# HDMI_to_RGB.net
KiCad netlist of a schematic drawn in Altium Designer
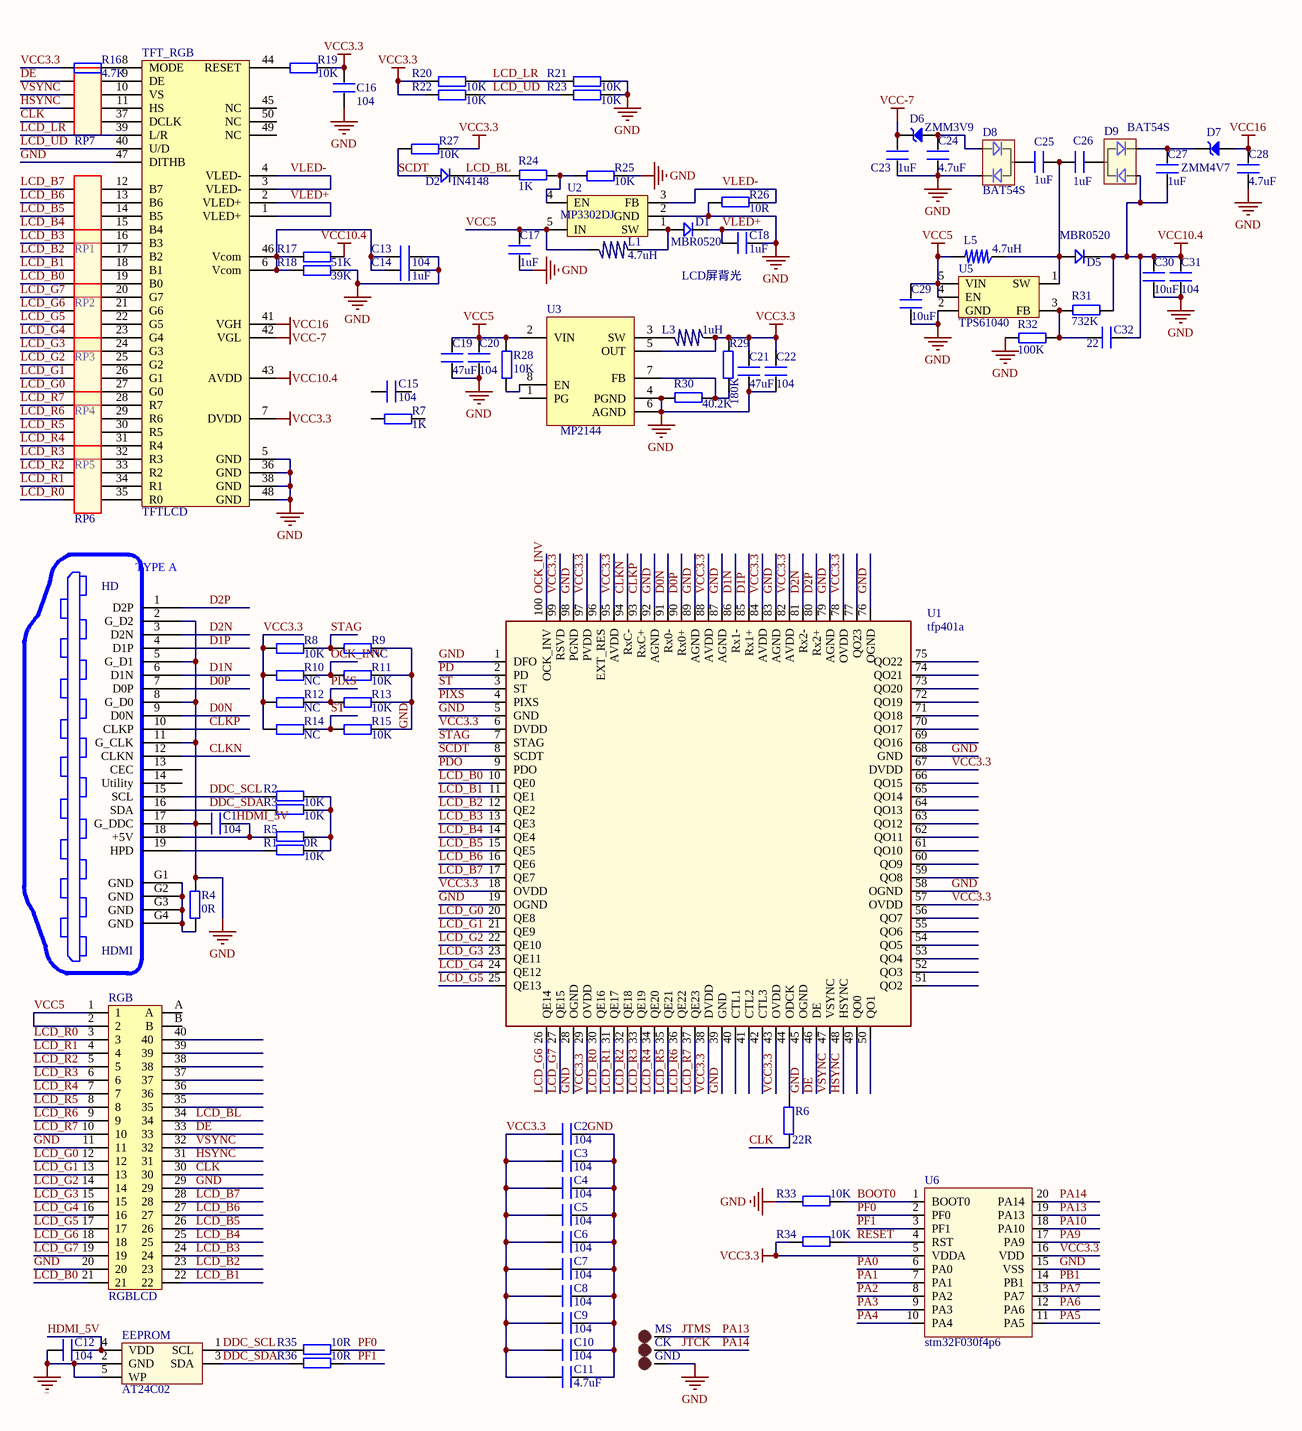
[diagram p0: HDMI_to_RGB.SchDoc]

(export (version "E")
  (design (tool "Eeschema 10.0.6"))
  (components
    (comp (ref "C1")
      (value "104")
      (footprint "C 0603_L")
      (libsource (lib "WarShip V3 STM32103封装库") (part "C"))
    )
    (comp (ref "C2")
      (value "104")
      (footprint "C 0603_L")
      (libsource (lib "WarShip V3 STM32103封装库") (part "C"))
    )
    (comp (ref "C3")
      (value "104")
      (footprint "C 0603_L")
      (libsource (lib "WarShip V3 STM32103封装库") (part "C"))
    )
    (comp (ref "C4")
      (value "104")
      (footprint "C 0603_L")
      (libsource (lib "WarShip V3 STM32103封装库") (part "C"))
    )
    (comp (ref "C5")
      (value "104")
      (footprint "C 0603_L")
      (libsource (lib "WarShip V3 STM32103封装库") (part "C"))
    )
    (comp (ref "C6")
      (value "104")
      (footprint "C 0603_L")
      (libsource (lib "WarShip V3 STM32103封装库") (part "C"))
    )
    (comp (ref "C7")
      (value "104")
      (footprint "C 0603_L")
      (libsource (lib "WarShip V3 STM32103封装库") (part "C"))
    )
    (comp (ref "C8")
      (value "104")
      (footprint "C 0603_L")
      (libsource (lib "WarShip V3 STM32103封装库") (part "C"))
    )
    (comp (ref "C9")
      (value "104")
      (footprint "C 0603_L")
      (libsource (lib "WarShip V3 STM32103封装库") (part "C"))
    )
    (comp (ref "C10")
      (value "104")
      (footprint "C 0603_L")
      (libsource (lib "WarShip V3 STM32103封装库") (part "C"))
    )
    (comp (ref "C11")
      (value "4.7uF")
      (footprint "C 0603_L")
      (libsource (lib "WarShip V3 STM32103封装库") (part "C"))
    )
    (comp (ref "C12")
      (value "104")
      (footprint "C 0603_L")
      (libsource (lib "WarShip V3 STM32103封装库") (part "C"))
    )
    (comp (ref "C13")
      (value "104")
      (footprint "C 0603_L")
      (libsource (lib "WarShip V3 STM32103封装库") (part "C"))
    )
    (comp (ref "C14")
      (value "1uF")
      (footprint "C 0603_L")
      (libsource (lib "WarShip V3 STM32103封装库") (part "C"))
    )
    (comp (ref "C15")
      (value "104")
      (footprint "C 0603_L")
      (libsource (lib "WarShip V3 STM32103封装库") (part "C"))
    )
    (comp (ref "C16")
      (value "104")
      (footprint "C 0603_L")
      (libsource (lib "WarShip V3 STM32103封装库") (part "C"))
    )
    (comp (ref "C17") (value "1uF") (footprint "C 0603_L") (libsource (lib "阿波罗STM32F4&F7底板封装库") (part "C")))
    (comp (ref "C18") (value "1uF") (footprint "C 0603_L") (libsource (lib "阿波罗STM32F4&F7底板封装库") (part "C")))
    (comp (ref "C19")
      (value "47uF")
      (footprint "C 0805_L")
      (libsource (lib "WarShip V3 STM32103封装库") (part "C"))
    )
    (comp (ref "C20")
      (value "104")
      (footprint "C 0603_L")
      (libsource (lib "WarShip V3 STM32103封装库") (part "C"))
    )
    (comp (ref "C21")
      (value "47uF")
      (footprint "C 0805_L")
      (libsource (lib "WarShip V3 STM32103封装库") (part "C"))
    )
    (comp (ref "C22")
      (value "104")
      (footprint "C 0603_L")
      (libsource (lib "WarShip V3 STM32103封装库") (part "C"))
    )
    (comp (ref "C23") (value "1uF") (footprint "C 0603_L") (libsource (lib "ALIENTEK_COMPONENT") (part "C")))
    (comp (ref "C24")
      (value "4.7uF")
      (footprint "C 0603_L")
      (libsource (lib "ALIENTEK_COMPONENT") (part "C"))
    )
    (comp (ref "C25") (value "1uF") (footprint "C 0603_L") (libsource (lib "ALIENTEK_COMPONENT") (part "C")))
    (comp (ref "C26") (value "1uF") (footprint "C 0603_L") (libsource (lib "ALIENTEK_COMPONENT") (part "C")))
    (comp (ref "C27") (value "1uF") (footprint "C 0603_L") (libsource (lib "ALIENTEK_COMPONENT") (part "C")))
    (comp (ref "C28")
      (value "4.7uF")
      (footprint "C 0603_L")
      (libsource (lib "ALIENTEK_COMPONENT") (part "C"))
    )
    (comp (ref "C29") (value "10uF") (footprint "C 0603_L") (libsource (lib "ALIENTEK_COMPONENT") (part "C")))
    (comp (ref "C30") (value "10uF") (footprint "C 0603_L") (libsource (lib "ALIENTEK_COMPONENT") (part "C")))
    (comp (ref "C31") (value "104") (footprint "C 0603_L") (libsource (lib "ALIENTEK_COMPONENT") (part "C")))
    (comp (ref "C32") (value "22") (footprint "C 0603_L") (libsource (lib "ALIENTEK_COMPONENT") (part "C")))
    (comp (ref "CK")
      (value "TEST POINT")
      (footprint "TP-1.5")
      (description "测试点")
      (libsource (lib "STM32F767核心板封装库") (part "TEST-POINT"))
    )
    (comp (ref "D1")
      (value "MBR0520")
      (footprint "二极管-整流桥:SOD-123")
      (description "1N4148")
      (libsource (lib "ATK-4.3' TFTLCD电容触摸屏模块_V1.2") (part "D"))
    )
    (comp (ref "D2")
      (value "IN4148")
      (footprint "二极管-整流桥:SOD-123")
      (description "1N4148")
      (libsource (lib "ATK-4.3' TFTLCD电容触摸屏模块_V1.2") (part "D"))
    )
    (comp (ref "D5")
      (value "MBR0520")
      (footprint "二极管-整流桥:SOD-123")
      (description "1N4148")
      (libsource (lib "ALIENTEK_COMPONENT") (part "D"))
    )
    (comp (ref "D6")
      (value "ZMM3V9")
      (footprint "DIODE_ZMMx")
      (description "ZMM3V6")
      (libsource (lib "ALIENTEK_COMPONENT") (part "ZMM3V6"))
    )
    (comp (ref "D7")
      (value "ZMM4V7")
      (footprint "DIODE_ZMMx")
      (description "ZMM3V6")
      (libsource (lib "ALIENTEK_COMPONENT") (part "ZMM3V6"))
    )
    (comp (ref "D8")
      (value "BAT54S")
      (footprint "SOT-23")
      (description "双肖特基二极管")
      (libsource (lib "") (part "BAT54S_1"))
    )
    (comp (ref "D9")
      (value "BAT54S")
      (footprint "SOT-23")
      (description "双肖特基二极管")
      (libsource (lib "ALIENTEK_COMPONENT") (part "BAT54S"))
    )
    (comp (ref "EEPROM")
      (value "AT24C02")
      (footprint "AT24C02")
      (libsource (lib "stm32f767igt6simple") (part "AT24C02"))
    )
    (comp (ref "GND")
      (value "TEST POINT")
      (footprint "TP-1.5")
      (description "测试点")
      (libsource (lib "STM32F767核心板封装库") (part "TEST-POINT"))
    )
    (comp (ref "HD")
      (value "HDMI")
      (footprint "HDMI_A")
      (libsource (lib "stm32f767igt6simple") (part "HDMI"))
    )
    (comp (ref "L1")
      (value "4.7uH")
      (footprint "NR4010")
      (libsource (lib "ATK-4.3' TFTLCD电容触摸屏模块_V1.2") (part "L"))
    )
    (comp (ref "L3") (value "1uH") (footprint "NR3015") (libsource (lib "MiniFly ") (part "L")))
    (comp (ref "L5")
      (value "4.7uH")
      (footprint "NR4010")
      (libsource (lib "ALIENTEK_COMPONENT") (part "L_SOP"))
    )
    (comp (ref "MS")
      (value "TEST POINT")
      (footprint "TP-1.5")
      (description "测试点")
      (libsource (lib "STM32F767核心板封装库") (part "TEST-POINT"))
    )
    (comp (ref "R1")
      (value "10K")
      (footprint "R 0603_L")
      (libsource (lib "WarShip V3 STM32103封装库") (part "R"))
    )
    (comp (ref "R2")
      (value "10K")
      (footprint "R 0603_L")
      (libsource (lib "WarShip V3 STM32103封装库") (part "R"))
    )
    (comp (ref "R3")
      (value "10K")
      (footprint "R 0603_L")
      (libsource (lib "WarShip V3 STM32103封装库") (part "R"))
    )
    (comp (ref "R4")
      (value "0R")
      (footprint "R 0603_L")
      (libsource (lib "WarShip V3 STM32103封装库") (part "R"))
    )
    (comp (ref "R5")
      (value "0R")
      (footprint "R 0603_L")
      (libsource (lib "WarShip V3 STM32103封装库") (part "R"))
    )
    (comp (ref "R6")
      (value "22R")
      (footprint "R 0603_L")
      (libsource (lib "WarShip V3 STM32103封装库") (part "R"))
    )
    (comp (ref "R7")
      (value "1K")
      (footprint "R 0603_L")
      (libsource (lib "WarShip V3 STM32103封装库") (part "R"))
    )
    (comp (ref "R8")
      (value "10K")
      (footprint "R 0603_L")
      (libsource (lib "WarShip V3 STM32103封装库") (part "R"))
    )
    (comp (ref "R9")
      (value "NC")
      (footprint "R 0603_L")
      (libsource (lib "WarShip V3 STM32103封装库") (part "R"))
    )
    (comp (ref "R10")
      (value "NC")
      (footprint "R 0603_L")
      (libsource (lib "WarShip V3 STM32103封装库") (part "R"))
    )
    (comp (ref "R11")
      (value "10K")
      (footprint "R 0603_L")
      (libsource (lib "WarShip V3 STM32103封装库") (part "R"))
    )
    (comp (ref "R12")
      (value "NC")
      (footprint "R 0603_L")
      (libsource (lib "WarShip V3 STM32103封装库") (part "R"))
    )
    (comp (ref "R13")
      (value "10K")
      (footprint "R 0603_L")
      (libsource (lib "WarShip V3 STM32103封装库") (part "R"))
    )
    (comp (ref "R14")
      (value "NC")
      (footprint "R 0603_L")
      (libsource (lib "WarShip V3 STM32103封装库") (part "R"))
    )
    (comp (ref "R15")
      (value "10K")
      (footprint "R 0603_L")
      (libsource (lib "WarShip V3 STM32103封装库") (part "R"))
    )
    (comp (ref "R16")
      (value "4.7K")
      (footprint "R 0603_L")
      (libsource (lib "WarShip V3 STM32103封装库") (part "R"))
    )
    (comp (ref "R17")
      (value "51K")
      (footprint "R 0603_L")
      (libsource (lib "WarShip V3 STM32103封装库") (part "R"))
    )
    (comp (ref "R18")
      (value "39K")
      (footprint "R 0603_L")
      (libsource (lib "WarShip V3 STM32103封装库") (part "R"))
    )
    (comp (ref "R19")
      (value "10K")
      (footprint "R 0603_L")
      (libsource (lib "WarShip V3 STM32103封装库") (part "R"))
    )
    (comp (ref "R20")
      (value "10K")
      (footprint "R 0603_L")
      (libsource (lib "WarShip V3 STM32103封装库") (part "R"))
    )
    (comp (ref "R21")
      (value "10K")
      (footprint "R 0603_L")
      (libsource (lib "WarShip V3 STM32103封装库") (part "R"))
    )
    (comp (ref "R22")
      (value "10K")
      (footprint "R 0603_L")
      (libsource (lib "WarShip V3 STM32103封装库") (part "R"))
    )
    (comp (ref "R23")
      (value "10K")
      (footprint "R 0603_L")
      (libsource (lib "WarShip V3 STM32103封装库") (part "R"))
    )
    (comp (ref "R24") (value "1K") (footprint "R 0603_L") (libsource (lib "阿波罗STM32F4&F7底板封装库") (part "R")))
    (comp (ref "R25") (value "10K") (footprint "R 0603_L") (libsource (lib "阿波罗STM32F4&F7底板封装库") (part "R")))
    (comp (ref "R26") (value "10R") (footprint "R 0603_L") (libsource (lib "阿波罗STM32F4&F7底板封装库") (part "R")))
    (comp (ref "R27")
      (value "10K")
      (footprint "R 0603_L")
      (libsource (lib "WarShip V3 STM32103封装库") (part "R"))
    )
    (comp (ref "R28") (value "10K") (footprint "R 0603_L") (libsource (lib "阿波罗STM32F4&F7底板封装库") (part "R")))
    (comp (ref "R29") (value "180K") (footprint "R 0603_L") (libsource (lib "电阻-电容-电感") (part "R")))
    (comp (ref "R30") (value "40.2K") (footprint "R 0603_L") (libsource (lib "电阻-电容-电感") (part "R")))
    (comp (ref "R31") (value "732K") (footprint "R 0603_L") (libsource (lib "ALIENTEK_COMPONENT") (part "R")))
    (comp (ref "R32") (value "100K") (footprint "R 0603_L") (libsource (lib "ALIENTEK_COMPONENT") (part "R")))
    (comp (ref "R33")
      (value "10K")
      (footprint "R 0603_L")
      (libsource (lib "WarShip V3 STM32103封装库") (part "R"))
    )
    (comp (ref "R34")
      (value "10K")
      (footprint "R 0603_L")
      (libsource (lib "WarShip V3 STM32103封装库") (part "R"))
    )
    (comp (ref "R35")
      (value "10R")
      (footprint "R 0603_L")
      (libsource (lib "WarShip V3 STM32103封装库") (part "R"))
    )
    (comp (ref "R36")
      (value "10R")
      (footprint "R 0603_L")
      (libsource (lib "WarShip V3 STM32103封装库") (part "R"))
    )
    (comp (ref "RGB")
      (value "RGBLCD")
      (footprint "FPC0.5 2H-WS-40P")
      (description "FPC-40P-0.5mm")
      (libsource (lib "STM32F429核心板封装库") (part "FPC-40"))
    )
    (comp (ref "RP1")
      (value "33R")
      (footprint "P_pack")
      (libsource (lib "stm32f767igt6simple") (part "R_pack"))
    )
    (comp (ref "RP2")
      (value "33R")
      (footprint "P_pack")
      (libsource (lib "stm32f767igt6simple") (part "R_pack"))
    )
    (comp (ref "RP3")
      (value "33R")
      (footprint "P_pack")
      (libsource (lib "stm32f767igt6simple") (part "R_pack"))
    )
    (comp (ref "RP4")
      (value "33R")
      (footprint "P_pack")
      (libsource (lib "stm32f767igt6simple") (part "R_pack"))
    )
    (comp (ref "RP5")
      (value "33R")
      (footprint "P_pack")
      (libsource (lib "stm32f767igt6simple") (part "R_pack"))
    )
    (comp (ref "RP6")
      (value "33R")
      (footprint "P_pack")
      (libsource (lib "stm32f767igt6simple") (part "R_pack"))
    )
    (comp (ref "RP7")
      (value "33R")
      (footprint "P_pack")
      (libsource (lib "stm32f767igt6simple") (part "R_pack"))
    )
    (comp (ref "TFT_RGB")
      (value "TFTLCD")
      (footprint "FPC-TOP50")
      (description "7' TFTLCD")
      (libsource (lib "ATK-7016&7084 7寸RGB屏模块封装库") (part "AT070TN92"))
    )
    (comp (ref "U1")
      (value "tfp401a")
      (footprint "LQFP100")
      (libsource (lib "stm32f767igt6simple") (part "tfp401a"))
    )
    (comp (ref "U2")
      (value "MP3302DJ")
      (footprint "SOT:SOT23-5L")
      (description "LCD背光IC")
      (libsource (lib "ATK-4.3' TFTLCD电容触摸屏模块_V1.2") (part "MP3302"))
    )
    (comp (ref "U3") (value "MP2144") (footprint "SOT23-8L") (libsource (lib "LDO和DCDC") (part "MP2144")))
    (comp (ref "U5")
      (value "TPS61040")
      (footprint "SOT:SOT23-5L")
      (description "DC DC Step Up IC")
      (libsource (lib "ALIENTEK_COMPONENT") (part "TPS61040"))
    )
    (comp (ref "U6")
      (value "stm32F030f4p6")
      (footprint "TSSOP20_N")
      (libsource (lib "oled_model") (part "stm32f030"))
    )
  )
  (nets
    (net (code "1") (name "/BOOT0") (class "Default")
      (node (ref "R33") (pin "1") (pintype "passive"))
      (node (ref "U6") (pin "1") (pinfunction "BOOT0_1") (pintype "passive"))
    )
    (net (code "2") (name "/CLK") (class "Default")
      (node (ref "R6") (pin "2") (pintype "passive"))
      (node (ref "RGB") (pin "30") (pinfunction "30_30") (pintype "passive"))
      (node (ref "RP7") (pin "7") (pintype "passive"))
    )
    (net (code "3") (name "/CLKN") (class "Default")
      (node (ref "HD") (pin "12") (pinfunction "CLKN_12") (pintype "passive"))
      (node (ref "U1") (pin "94") (pinfunction "RxC-_94") (pintype "passive"))
    )
    (net (code "4") (name "/CLKP") (class "Default")
      (node (ref "HD") (pin "10") (pinfunction "CLKP_10") (pintype "passive"))
      (node (ref "U1") (pin "93") (pinfunction "RxC+_93") (pintype "passive"))
    )
    (net (code "5") (name "/D0N") (class "Default")
      (node (ref "HD") (pin "9") (pinfunction "D0N_9") (pintype "passive"))
      (node (ref "U1") (pin "91") (pinfunction "Rx0-_91") (pintype "passive"))
    )
    (net (code "6") (name "/D0P") (class "Default")
      (node (ref "HD") (pin "7") (pinfunction "D0P_7") (pintype "passive"))
      (node (ref "U1") (pin "90") (pinfunction "Rx0+_90") (pintype "passive"))
    )
    (net (code "7") (name "/D1N") (class "Default")
      (node (ref "HD") (pin "6") (pinfunction "D1N_6") (pintype "passive"))
      (node (ref "U1") (pin "86") (pinfunction "Rx1-_86") (pintype "passive"))
    )
    (net (code "8") (name "/D1P") (class "Default")
      (node (ref "HD") (pin "4") (pinfunction "D1P_4") (pintype "passive"))
      (node (ref "U1") (pin "85") (pinfunction "Rx1+_85") (pintype "passive"))
    )
    (net (code "9") (name "/D2N") (class "Default")
      (node (ref "HD") (pin "3") (pinfunction "D2N_3") (pintype "passive"))
      (node (ref "U1") (pin "81") (pinfunction "Rx2-_81") (pintype "passive"))
    )
    (net (code "10") (name "/D2P") (class "Default")
      (node (ref "HD") (pin "1") (pinfunction "D2P_1") (pintype "passive"))
      (node (ref "U1") (pin "80") (pinfunction "Rx2+_80") (pintype "passive"))
    )
    (net (code "11") (name "/DDC_SCL") (class "Default")
      (node (ref "EEPROM") (pin "1") (pinfunction "SCL_1") (pintype "passive"))
      (node (ref "HD") (pin "15") (pinfunction "SCL_15") (pintype "passive"))
      (node (ref "R2") (pin "2") (pintype "passive"))
      (node (ref "R35") (pin "2") (pintype "passive"))
    )
    (net (code "12") (name "/DDC_SDA") (class "Default")
      (node (ref "EEPROM") (pin "3") (pinfunction "SDA_3") (pintype "passive"))
      (node (ref "HD") (pin "16") (pinfunction "SDA_16") (pintype "passive"))
      (node (ref "R3") (pin "2") (pintype "passive"))
      (node (ref "R36") (pin "2") (pintype "passive"))
    )
    (net (code "13") (name "/DE") (class "Default")
      (node (ref "RGB") (pin "33") (pinfunction "33_33") (pintype "passive"))
      (node (ref "RP7") (pin "1") (pinfunction "1_1") (pintype "passive"))
      (node (ref "U1") (pin "46") (pinfunction "DE_46") (pintype "passive"))
    )
    (net (code "14") (name "/HDMI_5V") (class "Default")
      (node (ref "C1") (pin "1") (pintype "passive"))
      (node (ref "C12") (pin "2") (pintype "passive"))
      (node (ref "EEPROM") (pin "4") (pinfunction "VDD_4") (pintype "passive"))
      (node (ref "HD") (pin "18") (pinfunction "+5V_18") (pintype "passive"))
      (node (ref "R5") (pin "2") (pintype "passive"))
    )
    (net (code "15") (name "/HSYNC") (class "Default")
      (node (ref "RGB") (pin "31") (pinfunction "31_31") (pintype "passive"))
      (node (ref "RP7") (pin "5") (pintype "passive"))
      (node (ref "U1") (pin "48") (pinfunction "HSYNC_48") (pintype "passive"))
    )
    (net (code "16") (name "/JTCK") (class "Default")
      (node (ref "CK") (pin "1") (pinfunction "1_1") (pintype "passive"))
      (node (ref "U6") (pin "20") (pinfunction "PA14_20") (pintype "passive"))
    )
    (net (code "17") (name "/JTMS") (class "Default")
      (node (ref "MS") (pin "1") (pinfunction "1_1") (pintype "passive"))
      (node (ref "U6") (pin "19") (pinfunction "PA13_19") (pintype "passive"))
    )
    (net (code "18") (name "/LCD_B0") (class "Default")
      (node (ref "RGB") (pin "21") (pinfunction "21_21") (pintype "passive"))
      (node (ref "RP2") (pin "7") (pintype "passive"))
      (node (ref "U1") (pin "10") (pinfunction "QE0_10") (pintype "passive"))
    )
    (net (code "19") (name "/LCD_B1") (class "Default")
      (node (ref "RGB") (pin "22") (pinfunction "22_22") (pintype "passive"))
      (node (ref "RP2") (pin "5") (pintype "passive"))
      (node (ref "U1") (pin "11") (pinfunction "QE1_11") (pintype "passive"))
    )
    (net (code "20") (name "/LCD_B2") (class "Default")
      (node (ref "RGB") (pin "23") (pinfunction "23_23") (pintype "passive"))
      (node (ref "RP2") (pin "3") (pintype "passive"))
      (node (ref "U1") (pin "12") (pinfunction "QE2_12") (pintype "passive"))
    )
    (net (code "21") (name "/LCD_B3") (class "Default")
      (node (ref "RGB") (pin "24") (pinfunction "24_24") (pintype "passive"))
      (node (ref "RP2") (pin "1") (pinfunction "1_1") (pintype "passive"))
      (node (ref "U1") (pin "13") (pinfunction "QE3_13") (pintype "passive"))
    )
    (net (code "22") (name "/LCD_B4") (class "Default")
      (node (ref "RGB") (pin "25") (pinfunction "25_25") (pintype "passive"))
      (node (ref "RP1") (pin "7") (pintype "passive"))
      (node (ref "U1") (pin "14") (pinfunction "QE4_14") (pintype "passive"))
    )
    (net (code "23") (name "/LCD_B5") (class "Default")
      (node (ref "RGB") (pin "26") (pinfunction "26_26") (pintype "passive"))
      (node (ref "RP1") (pin "5") (pintype "passive"))
      (node (ref "U1") (pin "15") (pinfunction "QE5_15") (pintype "passive"))
    )
    (net (code "24") (name "/LCD_B6") (class "Default")
      (node (ref "RGB") (pin "27") (pinfunction "27_27") (pintype "passive"))
      (node (ref "RP1") (pin "3") (pintype "passive"))
      (node (ref "U1") (pin "16") (pinfunction "QE6_16") (pintype "passive"))
    )
    (net (code "25") (name "/LCD_B7") (class "Default")
      (node (ref "RGB") (pin "28") (pinfunction "28_28") (pintype "passive"))
      (node (ref "RP1") (pin "1") (pinfunction "1_1") (pintype "passive"))
      (node (ref "U1") (pin "17") (pinfunction "QE7_17") (pintype "passive"))
    )
    (net (code "26") (name "/LCD_BL") (class "Default")
      (node (ref "D2") (pin "2") (pintype "passive"))
      (node (ref "R24") (pin "2") (pintype "passive"))
      (node (ref "RGB") (pin "34") (pinfunction "34_34") (pintype "passive"))
    )
    (net (code "27") (name "/LCD_G0") (class "Default")
      (node (ref "RGB") (pin "12") (pinfunction "12_12") (pintype "passive"))
      (node (ref "RP4") (pin "7") (pintype "passive"))
      (node (ref "U1") (pin "20") (pinfunction "QE8_20") (pintype "passive"))
    )
    (net (code "28") (name "/LCD_G1") (class "Default")
      (node (ref "RGB") (pin "13") (pinfunction "13_13") (pintype "passive"))
      (node (ref "RP4") (pin "5") (pintype "passive"))
      (node (ref "U1") (pin "21") (pinfunction "QE9_21") (pintype "passive"))
    )
    (net (code "29") (name "/LCD_G2") (class "Default")
      (node (ref "RGB") (pin "14") (pinfunction "14_14") (pintype "passive"))
      (node (ref "RP4") (pin "3") (pintype "passive"))
      (node (ref "U1") (pin "22") (pinfunction "QE10_22") (pintype "passive"))
    )
    (net (code "30") (name "/LCD_G3") (class "Default")
      (node (ref "RGB") (pin "15") (pinfunction "15_15") (pintype "passive"))
      (node (ref "RP4") (pin "1") (pinfunction "1_1") (pintype "passive"))
      (node (ref "U1") (pin "23") (pinfunction "QE11_23") (pintype "passive"))
    )
    (net (code "31") (name "/LCD_G4") (class "Default")
      (node (ref "RGB") (pin "16") (pinfunction "16_16") (pintype "passive"))
      (node (ref "RP3") (pin "7") (pintype "passive"))
      (node (ref "U1") (pin "24") (pinfunction "QE12_24") (pintype "passive"))
    )
    (net (code "32") (name "/LCD_G5") (class "Default")
      (node (ref "RGB") (pin "17") (pinfunction "17_17") (pintype "passive"))
      (node (ref "RP3") (pin "5") (pintype "passive"))
      (node (ref "U1") (pin "25") (pinfunction "QE13_25") (pintype "passive"))
    )
    (net (code "33") (name "/LCD_G6") (class "Default")
      (node (ref "RGB") (pin "18") (pinfunction "18_18") (pintype "passive"))
      (node (ref "RP3") (pin "3") (pintype "passive"))
      (node (ref "U1") (pin "26") (pinfunction "QE14_26") (pintype "passive"))
    )
    (net (code "34") (name "/LCD_G7") (class "Default")
      (node (ref "RGB") (pin "19") (pinfunction "19_19") (pintype "passive"))
      (node (ref "RP3") (pin "1") (pinfunction "1_1") (pintype "passive"))
      (node (ref "U1") (pin "27") (pinfunction "QE15_27") (pintype "passive"))
    )
    (net (code "35") (name "/LCD_LR") (class "Default")
      (node (ref "R20") (pin "2") (pintype "passive"))
      (node (ref "R21") (pin "1") (pintype "passive"))
      (node (ref "TFT_RGB") (pin "39") (pinfunction "L/R_39") (pintype "passive"))
    )
    (net (code "36") (name "/LCD_R0") (class "Default")
      (node (ref "RGB") (pin "3") (pinfunction "3_3") (pintype "passive"))
      (node (ref "RP6") (pin "7") (pintype "passive"))
      (node (ref "U1") (pin "30") (pinfunction "QE16_30") (pintype "passive"))
    )
    (net (code "37") (name "/LCD_R1") (class "Default")
      (node (ref "RGB") (pin "4") (pinfunction "4_4") (pintype "passive"))
      (node (ref "RP6") (pin "5") (pintype "passive"))
      (node (ref "U1") (pin "31") (pinfunction "QE17_31") (pintype "passive"))
    )
    (net (code "38") (name "/LCD_R2") (class "Default")
      (node (ref "RGB") (pin "5") (pinfunction "5_5") (pintype "passive"))
      (node (ref "RP6") (pin "3") (pintype "passive"))
      (node (ref "U1") (pin "32") (pinfunction "QE18_32") (pintype "passive"))
    )
    (net (code "39") (name "/LCD_R3") (class "Default")
      (node (ref "RGB") (pin "6") (pinfunction "6_6") (pintype "passive"))
      (node (ref "RP6") (pin "1") (pinfunction "1_1") (pintype "passive"))
      (node (ref "U1") (pin "33") (pinfunction "QE19_33") (pintype "passive"))
    )
    (net (code "40") (name "/LCD_R4") (class "Default")
      (node (ref "RGB") (pin "7") (pinfunction "7_7") (pintype "passive"))
      (node (ref "RP5") (pin "7") (pintype "passive"))
      (node (ref "U1") (pin "34") (pinfunction "QE20_34") (pintype "passive"))
    )
    (net (code "41") (name "/LCD_R5") (class "Default")
      (node (ref "RGB") (pin "8") (pinfunction "8_8") (pintype "passive"))
      (node (ref "RP5") (pin "5") (pintype "passive"))
      (node (ref "U1") (pin "35") (pinfunction "QE21_35") (pintype "passive"))
    )
    (net (code "42") (name "/LCD_R6") (class "Default")
      (node (ref "RGB") (pin "9") (pinfunction "9_9") (pintype "passive"))
      (node (ref "RP5") (pin "3") (pintype "passive"))
      (node (ref "U1") (pin "36") (pinfunction "QE22_36") (pintype "passive"))
    )
    (net (code "43") (name "/LCD_R7") (class "Default")
      (node (ref "RGB") (pin "10") (pinfunction "10_10") (pintype "passive"))
      (node (ref "RP5") (pin "1") (pinfunction "1_1") (pintype "passive"))
      (node (ref "U1") (pin "37") (pinfunction "QE23_37") (pintype "passive"))
    )
    (net (code "44") (name "/LCD_UD") (class "Default")
      (node (ref "R22") (pin "2") (pintype "passive"))
      (node (ref "R23") (pin "1") (pintype "passive"))
      (node (ref "TFT_RGB") (pin "40") (pinfunction "U/D_40") (pintype "passive"))
    )
    (net (code "45") (name "/OCK_INV") (class "Default")
      (node (ref "R10") (pin "2") (pintype "passive"))
      (node (ref "R11") (pin "1") (pintype "passive"))
      (node (ref "U1") (pin "100") (pinfunction "OCK_INV_100") (pintype "passive"))
    )
    (net (code "46") (name "/PA0") (class "Default")
      (node (ref "U6") (pin "6") (pinfunction "PA0_6") (pintype "passive"))
    )
    (net (code "47") (name "/PA1") (class "Default")
      (node (ref "U6") (pin "7") (pinfunction "PA1_7") (pintype "passive"))
    )
    (net (code "48") (name "/PA2") (class "Default")
      (node (ref "U6") (pin "8") (pinfunction "PA2_8") (pintype "passive"))
    )
    (net (code "49") (name "/PA3") (class "Default")
      (node (ref "U6") (pin "9") (pinfunction "PA3_9") (pintype "passive"))
    )
    (net (code "50") (name "/PA4") (class "Default")
      (node (ref "U6") (pin "10") (pinfunction "PA4_10") (pintype "passive"))
    )
    (net (code "51") (name "/PA5") (class "Default")
      (node (ref "U6") (pin "11") (pinfunction "PA5_11") (pintype "passive"))
    )
    (net (code "52") (name "/PA6") (class "Default")
      (node (ref "U6") (pin "12") (pinfunction "PA6_12") (pintype "passive"))
    )
    (net (code "53") (name "/PA7") (class "Default")
      (node (ref "U6") (pin "13") (pinfunction "PA7_13") (pintype "passive"))
    )
    (net (code "54") (name "/PA9") (class "Default")
      (node (ref "U6") (pin "17") (pinfunction "PA9_17") (pintype "passive"))
    )
    (net (code "55") (name "/PA10") (class "Default")
      (node (ref "U6") (pin "18") (pinfunction "PA10_18") (pintype "passive"))
    )
    (net (code "56") (name "/PB1") (class "Default")
      (node (ref "U6") (pin "14") (pinfunction "PB1_14") (pintype "passive"))
    )
    (net (code "57") (name "/PD") (class "Default")
      (node (ref "U1") (pin "2") (pinfunction "PD_2") (pintype "passive"))
    )
    (net (code "58") (name "/PDO") (class "Default")
      (node (ref "U1") (pin "9") (pinfunction "PDO_9") (pintype "passive"))
    )
    (net (code "59") (name "/PF0") (class "Default")
      (node (ref "R35") (pin "1") (pintype "passive"))
      (node (ref "U6") (pin "2") (pinfunction "PF0_2") (pintype "passive"))
    )
    (net (code "60") (name "/PF1") (class "Default")
      (node (ref "R36") (pin "1") (pintype "passive"))
      (node (ref "U6") (pin "3") (pinfunction "PF1_3") (pintype "passive"))
    )
    (net (code "61") (name "/PIXS") (class "Default")
      (node (ref "R12") (pin "2") (pintype "passive"))
      (node (ref "R13") (pin "1") (pintype "passive"))
      (node (ref "U1") (pin "4") (pinfunction "PIXS_4") (pintype "passive"))
    )
    (net (code "62") (name "/RESET") (class "Default")
      (node (ref "R34") (pin "1") (pintype "passive"))
      (node (ref "U6") (pin "4") (pinfunction "RST_4") (pintype "passive"))
    )
    (net (code "63") (name "/SCDT") (class "Default")
      (node (ref "D2") (pin "1") (pintype "passive"))
      (node (ref "R27") (pin "1") (pintype "passive"))
      (node (ref "U1") (pin "8") (pinfunction "SCDT_8") (pintype "passive"))
    )
    (net (code "64") (name "/ST") (class "Default")
      (node (ref "R14") (pin "2") (pintype "passive"))
      (node (ref "R15") (pin "1") (pintype "passive"))
      (node (ref "U1") (pin "3") (pinfunction "ST_3") (pintype "passive"))
    )
    (net (code "65") (name "/STAG") (class "Default")
      (node (ref "R8") (pin "2") (pintype "passive"))
      (node (ref "R9") (pin "1") (pintype "passive"))
      (node (ref "U1") (pin "7") (pinfunction "STAG_7") (pintype "passive"))
    )
    (net (code "66") (name "/VLED+") (class "Default")
      (node (ref "C18") (pin "2") (pintype "passive"))
      (node (ref "D1") (pin "2") (pintype "passive"))
      (node (ref "TFT_RGB") (pin "1") (pinfunction "VLED+_1") (pintype "passive"))
      (node (ref "TFT_RGB") (pin "2") (pinfunction "VLED+_2") (pintype "passive"))
    )
    (net (code "67") (name "/VLED-") (class "Default")
      (node (ref "R26") (pin "1") (pintype "passive"))
      (node (ref "TFT_RGB") (pin "3") (pinfunction "VLED-_3") (pintype "passive"))
      (node (ref "TFT_RGB") (pin "4") (pinfunction "VLED-_4") (pintype "passive"))
      (node (ref "U2") (pin "3") (pinfunction "FB_3") (pintype "passive"))
    )
    (net (code "68") (name "/VSYNC") (class "Default")
      (node (ref "RGB") (pin "32") (pinfunction "32_32") (pintype "passive"))
      (node (ref "RP7") (pin "3") (pintype "passive"))
      (node (ref "U1") (pin "47") (pinfunction "VSYNC_47") (pintype "passive"))
    )
    (net (code "69") (name "GND") (class "Default")
      (node (ref "C1") (pin "2") (pintype "passive"))
      (node (ref "C10") (pin "1") (pintype "passive"))
      (node (ref "C11") (pin "1") (pintype "passive"))
      (node (ref "C12") (pin "1") (pintype "passive"))
      (node (ref "C13") (pin "2") (pintype "passive"))
      (node (ref "C14") (pin "2") (pintype "passive"))
      (node (ref "C16") (pin "1") (pintype "passive"))
      (node (ref "C17") (pin "1") (pintype "passive"))
      (node (ref "C18") (pin "1") (pintype "passive"))
      (node (ref "C19") (pin "1") (pintype "passive"))
      (node (ref "C2") (pin "1") (pintype "passive"))
      (node (ref "C20") (pin "1") (pintype "passive"))
      (node (ref "C21") (pin "1") (pintype "passive"))
      (node (ref "C22") (pin "1") (pintype "passive"))
      (node (ref "C23") (pin "2") (pintype "passive"))
      (node (ref "C24") (pin "2") (pintype "passive"))
      (node (ref "C28") (pin "1") (pintype "passive"))
      (node (ref "C29") (pin "1") (pintype "passive"))
      (node (ref "C3") (pin "1") (pintype "passive"))
      (node (ref "C30") (pin "1") (pintype "passive"))
      (node (ref "C31") (pin "2") (pintype "passive"))
      (node (ref "C4") (pin "1") (pintype "passive"))
      (node (ref "C5") (pin "1") (pintype "passive"))
      (node (ref "C6") (pin "1") (pintype "passive"))
      (node (ref "C7") (pin "1") (pintype "passive"))
      (node (ref "C8") (pin "1") (pintype "passive"))
      (node (ref "C9") (pin "1") (pintype "passive"))
      (node (ref "D8") (pin "2") (pintype "passive"))
      (node (ref "EEPROM") (pin "2") (pinfunction "GND_2") (pintype "passive"))
      (node (ref "EEPROM") (pin "5") (pinfunction "WP_5") (pintype "passive"))
      (node (ref "GND") (pin "1") (pinfunction "1_1") (pintype "passive"))
      (node (ref "HD") (pin "11") (pinfunction "G_CLK_11") (pintype "passive"))
      (node (ref "HD") (pin "17") (pinfunction "G_DDC_17") (pintype "passive"))
      (node (ref "HD") (pin "2") (pinfunction "G_D2_2") (pintype "passive"))
      (node (ref "HD") (pin "5") (pinfunction "G_D1_5") (pintype "passive"))
      (node (ref "HD") (pin "8") (pinfunction "G_D0_8") (pintype "passive"))
      (node (ref "R11") (pin "2") (pintype "passive"))
      (node (ref "R13") (pin "2") (pintype "passive"))
      (node (ref "R15") (pin "2") (pintype "passive"))
      (node (ref "R18") (pin "2") (pintype "passive"))
      (node (ref "R21") (pin "2") (pintype "passive"))
      (node (ref "R23") (pin "2") (pintype "passive"))
      (node (ref "R25") (pin "2") (pintype "passive"))
      (node (ref "R26") (pin "2") (pintype "passive"))
      (node (ref "R30") (pin "2") (pintype "passive"))
      (node (ref "R32") (pin "1") (pintype "passive"))
      (node (ref "R33") (pin "2") (pintype "passive"))
      (node (ref "R4") (pin "1") (pintype "passive"))
      (node (ref "R9") (pin "2") (pintype "passive"))
      (node (ref "RGB") (pin "11") (pinfunction "11_11") (pintype "passive"))
      (node (ref "RGB") (pin "20") (pinfunction "20_20") (pintype "passive"))
      (node (ref "RGB") (pin "29") (pinfunction "29_29") (pintype "passive"))
      (node (ref "TFT_RGB") (pin "36") (pinfunction "GND_36") (pintype "passive"))
      (node (ref "TFT_RGB") (pin "38") (pinfunction "GND_38") (pintype "passive"))
      (node (ref "TFT_RGB") (pin "47") (pinfunction "DITHB_47") (pintype "passive"))
      (node (ref "TFT_RGB") (pin "48") (pinfunction "GND_48") (pintype "passive"))
      (node (ref "TFT_RGB") (pin "5") (pinfunction "GND_5") (pintype "passive"))
      (node (ref "U1") (pin "1") (pinfunction "DFO_1") (pintype "passive"))
      (node (ref "U1") (pin "19") (pinfunction "OGND_19") (pintype "passive"))
      (node (ref "U1") (pin "28") (pinfunction "OGND_28") (pintype "passive"))
      (node (ref "U1") (pin "39") (pinfunction "GND_39") (pintype "passive"))
      (node (ref "U1") (pin "45") (pinfunction "OGND_45") (pintype "passive"))
      (node (ref "U1") (pin "5") (pinfunction "GND_5") (pintype "passive"))
      (node (ref "U1") (pin "58") (pinfunction "OGND_58") (pintype "passive"))
      (node (ref "U1") (pin "68") (pinfunction "GND_68") (pintype "passive"))
      (node (ref "U1") (pin "76") (pinfunction "OGND_76") (pintype "passive"))
      (node (ref "U1") (pin "79") (pinfunction "AGND_79") (pintype "passive"))
      (node (ref "U1") (pin "83") (pinfunction "AGND_83") (pintype "passive"))
      (node (ref "U1") (pin "87") (pinfunction "AGND_87") (pintype "passive"))
      (node (ref "U1") (pin "89") (pinfunction "AGND_89") (pintype "passive"))
      (node (ref "U1") (pin "92") (pinfunction "AGND_92") (pintype "passive"))
      (node (ref "U1") (pin "98") (pinfunction "PGND_98") (pintype "passive"))
      (node (ref "U2") (pin "2") (pinfunction "GND_2") (pintype "passive"))
      (node (ref "U3") (pin "4") (pinfunction "PGND_4") (pintype "passive"))
      (node (ref "U3") (pin "6") (pinfunction "AGND_6") (pintype "passive"))
      (node (ref "U5") (pin "2") (pinfunction "GND_2") (pintype "passive"))
      (node (ref "U6") (pin "15") (pinfunction "VSS_15") (pintype "passive"))
    )
    (net (code "70") (name "Net-(C13-Pad1)") (class "Default")
      (node (ref "C13") (pin "1") (pintype "passive"))
      (node (ref "C14") (pin "1") (pintype "passive"))
      (node (ref "R17") (pin "1") (pintype "passive"))
      (node (ref "R18") (pin "1") (pintype "passive"))
      (node (ref "TFT_RGB") (pin "46") (pinfunction "Vcom_46") (pintype "passive"))
      (node (ref "TFT_RGB") (pin "6") (pinfunction "Vcom_6") (pintype "passive"))
    )
    (net (code "71") (name "Net-(C24-Pad1)") (class "Default")
      (node (ref "C24") (pin "1") (pintype "passive"))
      (node (ref "D6") (pin "1") (pintype "passive"))
      (node (ref "D8") (pin "1") (pintype "passive"))
    )
    (net (code "72") (name "Net-(C25-Pad1)") (class "Default")
      (node (ref "C25") (pin "1") (pintype "passive"))
      (node (ref "D8") (pin "3") (pintype "passive"))
    )
    (net (code "73") (name "Net-(C26-Pad2)") (class "Default")
      (node (ref "C26") (pin "2") (pintype "passive"))
      (node (ref "D9") (pin "3") (pintype "passive"))
    )
    (net (code "74") (name "Net-(C27-Pad2)") (class "Default")
      (node (ref "C27") (pin "2") (pintype "passive"))
      (node (ref "D7") (pin "2") (pintype "passive"))
      (node (ref "D9") (pin "2") (pintype "passive"))
    )
    (net (code "75") (name "Net-(HD-GND-PadG1)") (class "Default")
      (node (ref "HD") (pin "G1") (pinfunction "GND_G1") (pintype "passive"))
      (node (ref "HD") (pin "G2") (pinfunction "GND_G2") (pintype "passive"))
      (node (ref "HD") (pin "G3") (pinfunction "GND_G3") (pintype "passive"))
      (node (ref "HD") (pin "G4") (pinfunction "GND_G4") (pintype "passive"))
      (node (ref "R4") (pin "2") (pintype "passive"))
    )
    (net (code "76") (name "Net-(HD-HPD)") (class "Default")
      (node (ref "HD") (pin "19") (pinfunction "HPD_19") (pintype "passive"))
      (node (ref "R1") (pin "2") (pintype "passive"))
    )
    (net (code "77") (name "Net-(R1-Pad1)") (class "Default")
      (node (ref "R1") (pin "1") (pintype "passive"))
      (node (ref "R2") (pin "1") (pintype "passive"))
      (node (ref "R3") (pin "1") (pintype "passive"))
      (node (ref "R5") (pin "1") (pintype "passive"))
    )
    (net (code "78") (name "Net-(TFT_RGB-B0)") (class "Default")
      (node (ref "RP2") (pin "8") (pintype "passive"))
      (node (ref "TFT_RGB") (pin "19") (pinfunction "B0_19") (pintype "passive"))
    )
    (net (code "79") (name "Net-(TFT_RGB-B1)") (class "Default")
      (node (ref "RP2") (pin "6") (pintype "passive"))
      (node (ref "TFT_RGB") (pin "18") (pinfunction "B1_18") (pintype "passive"))
    )
    (net (code "80") (name "Net-(TFT_RGB-B2)") (class "Default")
      (node (ref "RP2") (pin "4") (pintype "passive"))
      (node (ref "TFT_RGB") (pin "17") (pinfunction "B2_17") (pintype "passive"))
    )
    (net (code "81") (name "Net-(TFT_RGB-B3)") (class "Default")
      (node (ref "RP2") (pin "2") (pintype "passive"))
      (node (ref "TFT_RGB") (pin "16") (pinfunction "B3_16") (pintype "passive"))
    )
    (net (code "82") (name "Net-(TFT_RGB-B4)") (class "Default")
      (node (ref "RP1") (pin "8") (pintype "passive"))
      (node (ref "TFT_RGB") (pin "15") (pinfunction "B4_15") (pintype "passive"))
    )
    (net (code "83") (name "Net-(TFT_RGB-B5)") (class "Default")
      (node (ref "RP1") (pin "6") (pintype "passive"))
      (node (ref "TFT_RGB") (pin "14") (pinfunction "B5_14") (pintype "passive"))
    )
    (net (code "84") (name "Net-(TFT_RGB-B6)") (class "Default")
      (node (ref "RP1") (pin "4") (pintype "passive"))
      (node (ref "TFT_RGB") (pin "13") (pinfunction "B6_13") (pintype "passive"))
    )
    (net (code "85") (name "Net-(TFT_RGB-B7)") (class "Default")
      (node (ref "RP1") (pin "2") (pintype "passive"))
      (node (ref "TFT_RGB") (pin "12") (pinfunction "B7_12") (pintype "passive"))
    )
    (net (code "86") (name "Net-(TFT_RGB-DCLK)") (class "Default")
      (node (ref "RP7") (pin "8") (pintype "passive"))
      (node (ref "TFT_RGB") (pin "37") (pinfunction "DCLK_37") (pintype "passive"))
    )
    (net (code "87") (name "Net-(TFT_RGB-DE)") (class "Default")
      (node (ref "RP7") (pin "2") (pintype "passive"))
      (node (ref "TFT_RGB") (pin "9") (pinfunction "DE_9") (pintype "passive"))
    )
    (net (code "88") (name "Net-(TFT_RGB-G0)") (class "Default")
      (node (ref "RP4") (pin "8") (pintype "passive"))
      (node (ref "TFT_RGB") (pin "27") (pinfunction "G0_27") (pintype "passive"))
    )
    (net (code "89") (name "Net-(TFT_RGB-G1)") (class "Default")
      (node (ref "RP4") (pin "6") (pintype "passive"))
      (node (ref "TFT_RGB") (pin "26") (pinfunction "G1_26") (pintype "passive"))
    )
    (net (code "90") (name "Net-(TFT_RGB-G2)") (class "Default")
      (node (ref "RP4") (pin "4") (pintype "passive"))
      (node (ref "TFT_RGB") (pin "25") (pinfunction "G2_25") (pintype "passive"))
    )
    (net (code "91") (name "Net-(TFT_RGB-G3)") (class "Default")
      (node (ref "RP4") (pin "2") (pintype "passive"))
      (node (ref "TFT_RGB") (pin "24") (pinfunction "G3_24") (pintype "passive"))
    )
    (net (code "92") (name "Net-(TFT_RGB-G4)") (class "Default")
      (node (ref "RP3") (pin "8") (pintype "passive"))
      (node (ref "TFT_RGB") (pin "23") (pinfunction "G4_23") (pintype "passive"))
    )
    (net (code "93") (name "Net-(TFT_RGB-G5)") (class "Default")
      (node (ref "RP3") (pin "6") (pintype "passive"))
      (node (ref "TFT_RGB") (pin "22") (pinfunction "G5_22") (pintype "passive"))
    )
    (net (code "94") (name "Net-(TFT_RGB-G6)") (class "Default")
      (node (ref "RP3") (pin "4") (pintype "passive"))
      (node (ref "TFT_RGB") (pin "21") (pinfunction "G6_21") (pintype "passive"))
    )
    (net (code "95") (name "Net-(TFT_RGB-G7)") (class "Default")
      (node (ref "RP3") (pin "2") (pintype "passive"))
      (node (ref "TFT_RGB") (pin "20") (pinfunction "G7_20") (pintype "passive"))
    )
    (net (code "96") (name "Net-(TFT_RGB-HS)") (class "Default")
      (node (ref "RP7") (pin "6") (pintype "passive"))
      (node (ref "TFT_RGB") (pin "11") (pinfunction "HS_11") (pintype "passive"))
    )
    (net (code "97") (name "Net-(TFT_RGB-MODE)") (class "Default")
      (node (ref "R16") (pin "2") (pintype "passive"))
      (node (ref "TFT_RGB") (pin "8") (pinfunction "MODE_8") (pintype "passive"))
    )
    (net (code "98") (name "Net-(TFT_RGB-R0)") (class "Default")
      (node (ref "RP6") (pin "8") (pintype "passive"))
      (node (ref "TFT_RGB") (pin "35") (pinfunction "R0_35") (pintype "passive"))
    )
    (net (code "99") (name "Net-(TFT_RGB-R1)") (class "Default")
      (node (ref "RP6") (pin "6") (pintype "passive"))
      (node (ref "TFT_RGB") (pin "34") (pinfunction "R1_34") (pintype "passive"))
    )
    (net (code "100") (name "Net-(TFT_RGB-R2)") (class "Default")
      (node (ref "RP6") (pin "4") (pintype "passive"))
      (node (ref "TFT_RGB") (pin "33") (pinfunction "R2_33") (pintype "passive"))
    )
    (net (code "101") (name "Net-(TFT_RGB-R3)") (class "Default")
      (node (ref "RP6") (pin "2") (pintype "passive"))
      (node (ref "TFT_RGB") (pin "32") (pinfunction "R3_32") (pintype "passive"))
    )
    (net (code "102") (name "Net-(TFT_RGB-R4)") (class "Default")
      (node (ref "RP5") (pin "8") (pintype "passive"))
      (node (ref "TFT_RGB") (pin "31") (pinfunction "R4_31") (pintype "passive"))
    )
    (net (code "103") (name "Net-(TFT_RGB-R5)") (class "Default")
      (node (ref "RP5") (pin "6") (pintype "passive"))
      (node (ref "TFT_RGB") (pin "30") (pinfunction "R5_30") (pintype "passive"))
    )
    (net (code "104") (name "Net-(TFT_RGB-R6)") (class "Default")
      (node (ref "RP5") (pin "4") (pintype "passive"))
      (node (ref "TFT_RGB") (pin "29") (pinfunction "R6_29") (pintype "passive"))
    )
    (net (code "105") (name "Net-(TFT_RGB-R7)") (class "Default")
      (node (ref "RP5") (pin "2") (pintype "passive"))
      (node (ref "TFT_RGB") (pin "28") (pinfunction "R7_28") (pintype "passive"))
    )
    (net (code "106") (name "Net-(TFT_RGB-RESET)") (class "Default")
      (node (ref "R19") (pin "1") (pintype "passive"))
      (node (ref "TFT_RGB") (pin "44") (pinfunction "RESET_44") (pintype "passive"))
    )
    (net (code "107") (name "Net-(TFT_RGB-VS)") (class "Default")
      (node (ref "RP7") (pin "4") (pintype "passive"))
      (node (ref "TFT_RGB") (pin "10") (pinfunction "VS_10") (pintype "passive"))
    )
    (net (code "108") (name "Net-(U1-ODCK)") (class "Default")
      (node (ref "R6") (pin "1") (pintype "passive"))
      (node (ref "U1") (pin "44") (pinfunction "ODCK_44") (pintype "passive"))
    )
    (net (code "109") (name "Net-(U2-EN)") (class "Default")
      (node (ref "R24") (pin "1") (pintype "passive"))
      (node (ref "R25") (pin "1") (pintype "passive"))
      (node (ref "U2") (pin "4") (pinfunction "EN_4") (pintype "passive"))
    )
    (net (code "110") (name "Net-(U2-SW)") (class "Default")
      (node (ref "D1") (pin "1") (pintype "passive"))
      (node (ref "L1") (pin "2") (pintype "passive"))
      (node (ref "U2") (pin "1") (pinfunction "SW_1") (pintype "passive"))
    )
    (net (code "111") (name "Net-(U3-EN)") (class "Default")
      (node (ref "R28") (pin "1") (pintype "passive"))
      (node (ref "U3") (pin "8") (pinfunction "EN_8") (pintype "passive"))
    )
    (net (code "112") (name "Net-(U3-FB)") (class "Default")
      (node (ref "R29") (pin "2") (pintype "passive"))
      (node (ref "R30") (pin "1") (pintype "passive"))
      (node (ref "U3") (pin "7") (pinfunction "FB_7") (pintype "passive"))
    )
    (net (code "113") (name "Net-(U3-SW)") (class "Default")
      (node (ref "L3") (pin "2") (pintype "passive"))
      (node (ref "U3") (pin "3") (pinfunction "SW_3") (pintype "passive"))
    )
    (net (code "114") (name "Net-(U5-FB)") (class "Default")
      (node (ref "C32") (pin "2") (pintype "passive"))
      (node (ref "R31") (pin "2") (pintype "passive"))
      (node (ref "R32") (pin "2") (pintype "passive"))
      (node (ref "U5") (pin "3") (pinfunction "FB_3") (pintype "passive"))
    )
    (net (code "115") (name "Net-(U5-SW)") (class "Default")
      (node (ref "C25") (pin "2") (pintype "passive"))
      (node (ref "C26") (pin "1") (pintype "passive"))
      (node (ref "D5") (pin "1") (pintype "passive"))
      (node (ref "L5") (pin "1") (pinfunction "1_1") (pintype "passive"))
      (node (ref "U5") (pin "1") (pinfunction "SW_1") (pintype "passive"))
    )
    (net (code "116") (name "VCC-7") (class "Default")
      (node (ref "C23") (pin "1") (pintype "passive"))
      (node (ref "D6") (pin "2") (pintype "passive"))
      (node (ref "TFT_RGB") (pin "42") (pinfunction "VGL_42") (pintype "passive"))
    )
    (net (code "117") (name "VCC3.3") (class "Default")
      (node (ref "C10") (pin "2") (pintype "passive"))
      (node (ref "C11") (pin "2") (pintype "passive"))
      (node (ref "C16") (pin "2") (pintype "passive"))
      (node (ref "C2") (pin "2") (pintype "passive"))
      (node (ref "C21") (pin "2") (pintype "passive"))
      (node (ref "C22") (pin "2") (pintype "passive"))
      (node (ref "C3") (pin "2") (pintype "passive"))
      (node (ref "C4") (pin "2") (pintype "passive"))
      (node (ref "C5") (pin "2") (pintype "passive"))
      (node (ref "C6") (pin "2") (pintype "passive"))
      (node (ref "C7") (pin "2") (pintype "passive"))
      (node (ref "C8") (pin "2") (pintype "passive"))
      (node (ref "C9") (pin "2") (pintype "passive"))
      (node (ref "L3") (pin "1") (pintype "passive"))
      (node (ref "R10") (pin "1") (pintype "passive"))
      (node (ref "R12") (pin "1") (pintype "passive"))
      (node (ref "R14") (pin "1") (pintype "passive"))
      (node (ref "R16") (pin "1") (pintype "passive"))
      (node (ref "R19") (pin "2") (pintype "passive"))
      (node (ref "R20") (pin "1") (pintype "passive"))
      (node (ref "R22") (pin "1") (pintype "passive"))
      (node (ref "R27") (pin "2") (pintype "passive"))
      (node (ref "R29") (pin "1") (pintype "passive"))
      (node (ref "R34") (pin "2") (pintype "passive"))
      (node (ref "R8") (pin "1") (pintype "passive"))
      (node (ref "TFT_RGB") (pin "7") (pinfunction "DVDD_7") (pintype "passive"))
      (node (ref "U1") (pin "18") (pinfunction "OVDD_18") (pintype "passive"))
      (node (ref "U1") (pin "29") (pinfunction "OVDD_29") (pintype "passive"))
      (node (ref "U1") (pin "38") (pinfunction "DVDD_38") (pintype "passive"))
      (node (ref "U1") (pin "43") (pinfunction "OVDD_43") (pintype "passive"))
      (node (ref "U1") (pin "57") (pinfunction "OVDD_57") (pintype "passive"))
      (node (ref "U1") (pin "6") (pinfunction "DVDD_6") (pintype "passive"))
      (node (ref "U1") (pin "67") (pinfunction "DVDD_67") (pintype "passive"))
      (node (ref "U1") (pin "78") (pinfunction "OVDD_78") (pintype "passive"))
      (node (ref "U1") (pin "82") (pinfunction "AVDD_82") (pintype "passive"))
      (node (ref "U1") (pin "84") (pinfunction "AVDD_84") (pintype "passive"))
      (node (ref "U1") (pin "88") (pinfunction "AVDD_88") (pintype "passive"))
      (node (ref "U1") (pin "95") (pinfunction "AVDD_95") (pintype "passive"))
      (node (ref "U1") (pin "97") (pinfunction "PVDD_97") (pintype "passive"))
      (node (ref "U1") (pin "99") (pinfunction "RSVD_99") (pintype "passive"))
      (node (ref "U3") (pin "5") (pinfunction "OUT_5") (pintype "passive"))
      (node (ref "U6") (pin "16") (pinfunction "VDD_16") (pintype "passive"))
      (node (ref "U6") (pin "5") (pinfunction "VDDA_5") (pintype "passive"))
    )
    (net (code "118") (name "VCC5") (class "Default")
      (node (ref "C17") (pin "2") (pintype "passive"))
      (node (ref "C19") (pin "2") (pintype "passive"))
      (node (ref "C20") (pin "2") (pintype "passive"))
      (node (ref "C29") (pin "2") (pintype "passive"))
      (node (ref "L1") (pin "1") (pintype "passive"))
      (node (ref "L5") (pin "2") (pinfunction "2_2") (pintype "passive"))
      (node (ref "R28") (pin "2") (pintype "passive"))
      (node (ref "RGB") (pin "1") (pinfunction "1_1") (pintype "passive"))
      (node (ref "RGB") (pin "2") (pinfunction "2_2") (pintype "passive"))
      (node (ref "U2") (pin "5") (pinfunction "IN_5") (pintype "passive"))
      (node (ref "U3") (pin "2") (pinfunction "VIN_2") (pintype "passive"))
      (node (ref "U5") (pin "4") (pinfunction "EN_4") (pintype "passive"))
      (node (ref "U5") (pin "5") (pinfunction "VIN_5") (pintype "passive"))
    )
    (net (code "119") (name "VCC10.4") (class "Default")
      (node (ref "C27") (pin "1") (pintype "passive"))
      (node (ref "C30") (pin "2") (pintype "passive"))
      (node (ref "C31") (pin "1") (pintype "passive"))
      (node (ref "C32") (pin "1") (pintype "passive"))
      (node (ref "D5") (pin "2") (pintype "passive"))
      (node (ref "D9") (pin "1") (pintype "passive"))
      (node (ref "R17") (pin "2") (pintype "passive"))
      (node (ref "R31") (pin "1") (pintype "passive"))
      (node (ref "TFT_RGB") (pin "43") (pinfunction "AVDD_43") (pintype "passive"))
    )
    (net (code "120") (name "VCC16") (class "Default")
      (node (ref "C28") (pin "2") (pintype "passive"))
      (node (ref "D7") (pin "1") (pintype "passive"))
      (node (ref "TFT_RGB") (pin "41") (pinfunction "VGH_41") (pintype "passive"))
    )
    (net (code "121") (name "unconnected-(C15-Pad1)") (class "Default")
      (node (ref "C15") (pin "1") (pintype "passive"))
    )
    (net (code "122") (name "unconnected-(C15-Pad2)") (class "Default")
      (node (ref "C15") (pin "2") (pintype "passive"))
    )
    (net (code "123") (name "unconnected-(HD-CEC-Pad13)") (class "Default")
      (node (ref "HD") (pin "13") (pinfunction "CEC_13") (pintype "passive"))
    )
    (net (code "124") (name "unconnected-(HD-Utility-Pad14)") (class "Default")
      (node (ref "HD") (pin "14") (pinfunction "Utility_14") (pintype "passive"))
    )
    (net (code "125") (name "unconnected-(R7-Pad1)") (class "Default")
      (node (ref "R7") (pin "1") (pintype "passive"))
    )
    (net (code "126") (name "unconnected-(R7-Pad2)") (class "Default")
      (node (ref "R7") (pin "2") (pintype "passive"))
    )
    (net (code "127") (name "unconnected-(RGB-Pad35)") (class "Default")
      (node (ref "RGB") (pin "35") (pinfunction "35_35") (pintype "passive"))
    )
    (net (code "128") (name "unconnected-(RGB-Pad36)") (class "Default")
      (node (ref "RGB") (pin "36") (pinfunction "36_36") (pintype "passive"))
    )
    (net (code "129") (name "unconnected-(RGB-Pad37)") (class "Default")
      (node (ref "RGB") (pin "37") (pinfunction "37_37") (pintype "passive"))
    )
    (net (code "130") (name "unconnected-(RGB-Pad38)") (class "Default")
      (node (ref "RGB") (pin "38") (pinfunction "38_38") (pintype "passive"))
    )
    (net (code "131") (name "unconnected-(RGB-Pad39)") (class "Default")
      (node (ref "RGB") (pin "39") (pinfunction "39_39") (pintype "passive"))
    )
    (net (code "132") (name "unconnected-(RGB-Pad40)") (class "Default")
      (node (ref "RGB") (pin "40") (pinfunction "40_40") (pintype "passive"))
    )
    (net (code "133") (name "unconnected-(RGB-PadA)") (class "Default")
      (node (ref "RGB") (pin "A") (pinfunction "A_A") (pintype "passive"))
    )
    (net (code "134") (name "unconnected-(RGB-PadB)") (class "Default")
      (node (ref "RGB") (pin "B") (pinfunction "B_B") (pintype "passive"))
    )
    (net (code "135") (name "unconnected-(TFT_RGB-NC-Pad45)") (class "Default")
      (node (ref "TFT_RGB") (pin "45") (pinfunction "NC_45") (pintype "passive"))
    )
    (net (code "136") (name "unconnected-(TFT_RGB-NC-Pad49)") (class "Default")
      (node (ref "TFT_RGB") (pin "49") (pinfunction "NC_49") (pintype "passive"))
    )
    (net (code "137") (name "unconnected-(TFT_RGB-NC-Pad50)") (class "Default")
      (node (ref "TFT_RGB") (pin "50") (pinfunction "NC_50") (pintype "passive"))
    )
    (net (code "138") (name "unconnected-(U1-CTL1-Pad40)") (class "Default")
      (node (ref "U1") (pin "40") (pinfunction "CTL1_40") (pintype "passive"))
    )
    (net (code "139") (name "unconnected-(U1-CTL2-Pad41)") (class "Default")
      (node (ref "U1") (pin "41") (pinfunction "CTL2_41") (pintype "passive"))
    )
    (net (code "140") (name "unconnected-(U1-CTL3-Pad42)") (class "Default")
      (node (ref "U1") (pin "42") (pinfunction "CTL3_42") (pintype "passive"))
    )
    (net (code "141") (name "unconnected-(U1-EXT_RES-Pad96)") (class "Default")
      (node (ref "U1") (pin "96") (pinfunction "EXT_RES_96") (pintype "passive"))
    )
    (net (code "142") (name "unconnected-(U1-QO0-Pad49)") (class "Default")
      (node (ref "U1") (pin "49") (pinfunction "QO0_49") (pintype "passive"))
    )
    (net (code "143") (name "unconnected-(U1-QO1-Pad50)") (class "Default")
      (node (ref "U1") (pin "50") (pinfunction "QO1_50") (pintype "passive"))
    )
    (net (code "144") (name "unconnected-(U1-QO2-Pad51)") (class "Default")
      (node (ref "U1") (pin "51") (pinfunction "QO2_51") (pintype "passive"))
    )
    (net (code "145") (name "unconnected-(U1-QO3-Pad52)") (class "Default")
      (node (ref "U1") (pin "52") (pinfunction "QO3_52") (pintype "passive"))
    )
    (net (code "146") (name "unconnected-(U1-QO4-Pad53)") (class "Default")
      (node (ref "U1") (pin "53") (pinfunction "QO4_53") (pintype "passive"))
    )
    (net (code "147") (name "unconnected-(U1-QO5-Pad54)") (class "Default")
      (node (ref "U1") (pin "54") (pinfunction "QO5_54") (pintype "passive"))
    )
    (net (code "148") (name "unconnected-(U1-QO6-Pad55)") (class "Default")
      (node (ref "U1") (pin "55") (pinfunction "QO6_55") (pintype "passive"))
    )
    (net (code "149") (name "unconnected-(U1-QO7-Pad56)") (class "Default")
      (node (ref "U1") (pin "56") (pinfunction "QO7_56") (pintype "passive"))
    )
    (net (code "150") (name "unconnected-(U1-QO8-Pad59)") (class "Default")
      (node (ref "U1") (pin "59") (pinfunction "QO8_59") (pintype "passive"))
    )
    (net (code "151") (name "unconnected-(U1-QO9-Pad60)") (class "Default")
      (node (ref "U1") (pin "60") (pinfunction "QO9_60") (pintype "passive"))
    )
    (net (code "152") (name "unconnected-(U1-QO10-Pad61)") (class "Default")
      (node (ref "U1") (pin "61") (pinfunction "QO10_61") (pintype "passive"))
    )
    (net (code "153") (name "unconnected-(U1-QO11-Pad62)") (class "Default")
      (node (ref "U1") (pin "62") (pinfunction "QO11_62") (pintype "passive"))
    )
    (net (code "154") (name "unconnected-(U1-QO12-Pad63)") (class "Default")
      (node (ref "U1") (pin "63") (pinfunction "QO12_63") (pintype "passive"))
    )
    (net (code "155") (name "unconnected-(U1-QO13-Pad64)") (class "Default")
      (node (ref "U1") (pin "64") (pinfunction "QO13_64") (pintype "passive"))
    )
    (net (code "156") (name "unconnected-(U1-QO14-Pad65)") (class "Default")
      (node (ref "U1") (pin "65") (pinfunction "QO14_65") (pintype "passive"))
    )
    (net (code "157") (name "unconnected-(U1-QO15-Pad66)") (class "Default")
      (node (ref "U1") (pin "66") (pinfunction "QO15_66") (pintype "passive"))
    )
    (net (code "158") (name "unconnected-(U1-QO16-Pad69)") (class "Default")
      (node (ref "U1") (pin "69") (pinfunction "QO16_69") (pintype "passive"))
    )
    (net (code "159") (name "unconnected-(U1-QO17-Pad70)") (class "Default")
      (node (ref "U1") (pin "70") (pinfunction "QO17_70") (pintype "passive"))
    )
    (net (code "160") (name "unconnected-(U1-QO18-Pad71)") (class "Default")
      (node (ref "U1") (pin "71") (pinfunction "QO18_71") (pintype "passive"))
    )
    (net (code "161") (name "unconnected-(U1-QO19-Pad72)") (class "Default")
      (node (ref "U1") (pin "72") (pinfunction "QO19_72") (pintype "passive"))
    )
    (net (code "162") (name "unconnected-(U1-QO20-Pad73)") (class "Default")
      (node (ref "U1") (pin "73") (pinfunction "QO20_73") (pintype "passive"))
    )
    (net (code "163") (name "unconnected-(U1-QO21-Pad74)") (class "Default")
      (node (ref "U1") (pin "74") (pinfunction "QO21_74") (pintype "passive"))
    )
    (net (code "164") (name "unconnected-(U1-QO22-Pad75)") (class "Default")
      (node (ref "U1") (pin "75") (pinfunction "QO22_75") (pintype "passive"))
    )
    (net (code "165") (name "unconnected-(U1-QO23-Pad77)") (class "Default")
      (node (ref "U1") (pin "77") (pinfunction "QO23_77") (pintype "passive"))
    )
    (net (code "166") (name "unconnected-(U3-PG-Pad1)") (class "Default")
      (node (ref "U3") (pin "1") (pinfunction "PG_1") (pintype "passive"))
    )
  )
)
